# RemoteControl.net
KiCad netlist of a schematic drawn in Altium Designer
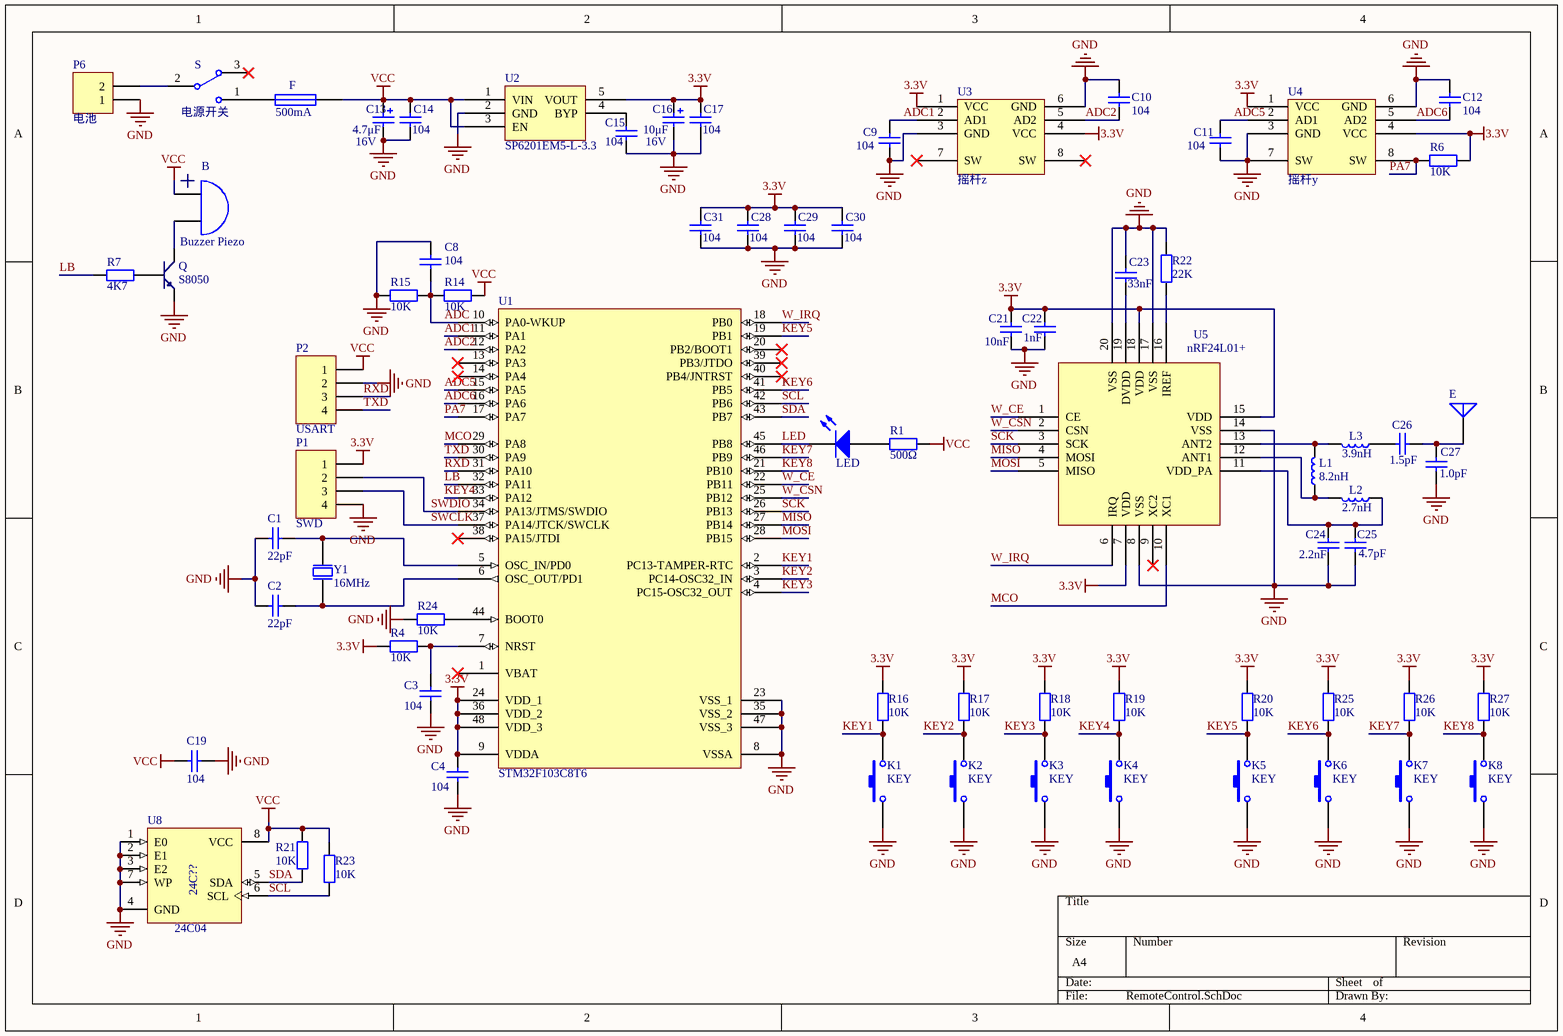
[diagram p0: RemoteControl.SchDoc]

(export (version "E")
  (design (tool "Eeschema 10.0.6"))
  (components
    (comp (ref "B")
      (value "Buzzer Piezo")
      (footprint "BUZZER")
      (description "Electrical Bell")
      (fields (field (name "PUBLISHER") "Altium Limited"))
      (libsource (lib "mini四轴") (part "Buzzer"))
    )
    (comp (ref "C1")
      (value "22pF")
      (footprint "CC1608-0603")
      (description "Capacitor")
      (fields (field (name "PUBLISHER") "Altium Limited"))
      (libsource (lib "mini四轴") (part "Cap"))
    )
    (comp (ref "C2")
      (value "22pF")
      (footprint "CC1608-0603")
      (description "Capacitor")
      (fields (field (name "PUBLISHER") "Altium Limited"))
      (libsource (lib "mini四轴") (part "Cap"))
    )
    (comp (ref "C3")
      (value "104")
      (footprint "CC1608-0603")
      (description "Capacitor")
      (fields (field (name "PUBLISHER") "Altium Limited"))
      (libsource (lib "mini四轴") (part "Cap"))
    )
    (comp (ref "C4")
      (value "104")
      (footprint "CC1608-0603")
      (description "Capacitor")
      (fields (field (name "PUBLISHER") "Altium Limited"))
      (libsource (lib "mini四轴") (part "Cap"))
    )
    (comp (ref "C8")
      (value "104")
      (footprint "CC1608-0603")
      (description "Capacitor")
      (fields (field (name "PUBLISHER") "Altium Limited"))
      (libsource (lib "mini四轴") (part "Cap"))
    )
    (comp (ref "C9")
      (value "104")
      (footprint "CC1608-0603")
      (description "Capacitor")
      (fields (field (name "PUBLISHER") "Altium Limited"))
      (libsource (lib "mini四轴") (part "Cap"))
    )
    (comp (ref "C10")
      (value "104")
      (footprint "CC1608-0603")
      (description "Capacitor")
      (fields (field (name "PUBLISHER") "Altium Limited"))
      (libsource (lib "mini四轴") (part "Cap"))
    )
    (comp (ref "C11")
      (value "104")
      (footprint "CC1608-0603")
      (description "Capacitor")
      (fields (field (name "PUBLISHER") "Altium Limited"))
      (libsource (lib "mini四轴") (part "Cap"))
    )
    (comp (ref "C12")
      (value "104")
      (footprint "CC1608-0603")
      (description "Capacitor")
      (fields (field (name "PUBLISHER") "Altium Limited"))
      (libsource (lib "mini四轴") (part "Cap"))
    )
    (comp (ref "C13")
      (value "4.7μF")
      (footprint "TAN-A-3216")
      (description "Polarized Capacitor (Radial)")
      (fields (field (name "VOLTAGE") "16V") (field (name "PUBLISHER") "Altium Limited"))
      (libsource (lib "我的集成库1") (part "Cap Tan"))
    )
    (comp (ref "C14")
      (value "104")
      (footprint "CC1608-0603")
      (description "Capacitor")
      (fields (field (name "PUBLISHER") "Altium Limited"))
      (libsource (lib "mini四轴") (part "Cap"))
    )
    (comp (ref "C15")
      (value "104")
      (footprint "CC1608-0603")
      (description "Capacitor")
      (fields (field (name "PUBLISHER") "Altium Limited"))
      (libsource (lib "mini四轴") (part "Cap"))
    )
    (comp (ref "C16")
      (value "10μF")
      (footprint "TAN-A-3216")
      (description "Polarized Capacitor (Radial)")
      (fields (field (name "VOLTAGE") "16V") (field (name "PUBLISHER") "Altium Limited"))
      (libsource (lib "我的集成库1") (part "Cap Tan"))
    )
    (comp (ref "C17")
      (value "104")
      (footprint "CC1608-0603")
      (description "Capacitor")
      (fields (field (name "PUBLISHER") "Altium Limited"))
      (libsource (lib "mini四轴") (part "Cap"))
    )
    (comp (ref "C19")
      (value "104")
      (footprint "CC1608-0603")
      (description "Polarized Capacitor (Radial)")
      (fields (field (name "PUBLISHER") "Altium Limited"))
      (libsource (lib "我的集成库1") (part "Cap Chip"))
    )
    (comp (ref "C21")
      (value "10nF")
      (footprint "CC1608-0603")
      (description "Capacitor")
      (fields (field (name "PUBLISHER") "Altium Limited"))
      (libsource (lib "mini四轴") (part "Cap"))
    )
    (comp (ref "C22")
      (value "1nF")
      (footprint "CC1608-0603")
      (description "Capacitor")
      (fields (field (name "PUBLISHER") "Altium Limited"))
      (libsource (lib "mini四轴") (part "Cap"))
    )
    (comp (ref "C23")
      (value "33nF")
      (footprint "CC1608-0603")
      (description "Capacitor")
      (fields (field (name "PUBLISHER") "Altium Limited"))
      (libsource (lib "mini四轴") (part "Cap"))
    )
    (comp (ref "C24")
      (value "2.2nF")
      (footprint "CC1608-0603")
      (description "Capacitor")
      (fields (field (name "PUBLISHER") "Altium Limited"))
      (libsource (lib "mini四轴") (part "Cap"))
    )
    (comp (ref "C25")
      (value "4.7pF")
      (footprint "CC1608-0603")
      (description "Capacitor")
      (fields (field (name "PUBLISHER") "Altium Limited"))
      (libsource (lib "mini四轴") (part "Cap"))
    )
    (comp (ref "C26")
      (value "1.5pF")
      (footprint "CC1608-0603")
      (description "Capacitor")
      (fields (field (name "PUBLISHER") "Altium Limited"))
      (libsource (lib "mini四轴") (part "Cap"))
    )
    (comp (ref "C27")
      (value "1.0pF")
      (footprint "CC1608-0603")
      (description "Capacitor")
      (fields (field (name "PUBLISHER") "Altium Limited"))
      (libsource (lib "mini四轴") (part "Cap"))
    )
    (comp (ref "C28")
      (value "104")
      (footprint "CC1608-0603")
      (description "Capacitor")
      (fields (field (name "PUBLISHER") "Altium Limited"))
      (libsource (lib "mini四轴") (part "Cap"))
    )
    (comp (ref "C29")
      (value "104")
      (footprint "CC1608-0603")
      (description "Capacitor")
      (fields (field (name "PUBLISHER") "Altium Limited"))
      (libsource (lib "mini四轴") (part "Cap"))
    )
    (comp (ref "C30")
      (value "104")
      (footprint "CC1608-0603")
      (description "Capacitor")
      (fields (field (name "PUBLISHER") "Altium Limited"))
      (libsource (lib "mini四轴") (part "Cap"))
    )
    (comp (ref "C31")
      (value "104")
      (footprint "CC1608-0603")
      (description "Capacitor")
      (fields (field (name "PUBLISHER") "Altium Limited"))
      (libsource (lib "mini四轴") (part "Cap"))
    )
    (comp (ref "E")
      (value "~")
      (footprint "Chip Antenna")
      (description "Generic Antenna")
      (fields (field (name "PUBLISHER") "Altium Limited"))
      (libsource (lib "mini四轴") (part "Antenna"))
    )
    (comp (ref "F")
      (value "500mA")
      (footprint "CR2012-0805")
      (description "Fuse")
      (fields (field (name "PUBLISHER") "Altium Limited"))
      (libsource (lib "我的集成库1") (part "Fuse"))
    )
    (comp (ref "K1") (value "KEY") (footprint "KEY2") (libsource (lib "我的集成库1") (part "KYE")))
    (comp (ref "K2") (value "KEY") (footprint "KEY2") (libsource (lib "我的集成库1") (part "KYE")))
    (comp (ref "K3") (value "KEY") (footprint "KEY2") (libsource (lib "我的集成库1") (part "KYE")))
    (comp (ref "K4") (value "KEY") (footprint "KEY2") (libsource (lib "我的集成库1") (part "KYE")))
    (comp (ref "K5") (value "KEY") (footprint "KEY2") (libsource (lib "我的集成库1") (part "KYE")))
    (comp (ref "K6") (value "KEY") (footprint "KEY2") (libsource (lib "我的集成库1") (part "KYE")))
    (comp (ref "K7") (value "KEY") (footprint "KEY2") (libsource (lib "我的集成库1") (part "KYE")))
    (comp (ref "K8") (value "KEY") (footprint "KEY2") (libsource (lib "我的集成库1") (part "KYE")))
    (comp (ref "L1")
      (value "8.2nH")
      (footprint "CC1608[0603]")
      (description "Inductor")
      (fields (field (name "PUBLISHER") "Altium Limited"))
      (libsource (lib "mini四轴") (part "Inductor"))
    )
    (comp (ref "L2")
      (value "2.7nH")
      (footprint "CC1608[0603]")
      (description "Inductor")
      (fields (field (name "PUBLISHER") "Altium Limited"))
      (libsource (lib "mini四轴") (part "Inductor"))
    )
    (comp (ref "L3")
      (value "3.9nH")
      (footprint "CC1608[0603]")
      (description "Inductor")
      (fields (field (name "PUBLISHER") "Altium Limited"))
      (libsource (lib "mini四轴") (part "Inductor"))
    )
    (comp (ref "LED")
      (value "LED Chip")
      (footprint "CLED1608-0603")
      (description "Typical Chip LED")
      (fields (field (name "PUBLISHER") "Altium Limited"))
      (libsource (lib "我的集成库1") (part "LED Chip"))
    )
    (comp (ref "P1")
      (value "SWD")
      (footprint "HDR1X4")
      (description "Header, 4-Pin")
      (fields (field (name "PUBLISHER") "Altium Limited"))
      (libsource (lib "我的集成库1") (part "Header 4"))
    )
    (comp (ref "P2")
      (value "USART")
      (footprint "HDR1X4")
      (description "Header, 4-Pin")
      (fields (field (name "PUBLISHER") "Altium Limited"))
      (libsource (lib "我的集成库1") (part "Header 4"))
    )
    (comp (ref "P6")
      (value "电池")
      (footprint "HDR1X2")
      (description "Header, 2-Pin")
      (fields (field (name "PUBLISHER") "Altium Limited"))
      (libsource (lib "我的集成库1") (part "Header 2"))
    )
    (comp (ref "Q")
      (value "S8050")
      (footprint "SOT-23")
      (description "8050/BCW846/BCW847")
      (libsource (lib "战舰STM32开发板底板封装库") (part "NPN"))
    )
    (comp (ref "R1")
      (value "500Ω")
      (footprint "CR1608-0603")
      (description "Resistor")
      (fields (field (name "PUBLISHER") "Altium Limited"))
      (libsource (lib "") (part "Resistor Chip_2"))
    )
    (comp (ref "R4")
      (value "10K")
      (footprint "CR1608-0603")
      (description "Resistor")
      (fields (field (name "PUBLISHER") "Altium Limited"))
      (libsource (lib "") (part "Resistor Chip_3"))
    )
    (comp (ref "R6")
      (value "10K")
      (footprint "CR1608-0603")
      (description "Resistor")
      (fields (field (name "PUBLISHER") "Altium Limited"))
      (libsource (lib "") (part "Resistor Chip_2"))
    )
    (comp (ref "R7")
      (value "4K7")
      (footprint "CR1608-0603")
      (description "Resistor")
      (fields (field (name "Comment") "10K") (field (name "PUBLISHER") "Altium Limited"))
      (libsource (lib "") (part "Resistor Chip_2"))
    )
    (comp (ref "R14")
      (value "10K")
      (footprint "CR1608-0603")
      (description "Resistor")
      (fields (field (name "PUBLISHER") "Altium Limited"))
      (libsource (lib "") (part "Resistor Chip_1"))
    )
    (comp (ref "R15")
      (value "10K")
      (footprint "CR1608-0603")
      (description "Resistor")
      (fields (field (name "PUBLISHER") "Altium Limited"))
      (libsource (lib "") (part "Resistor Chip_1"))
    )
    (comp (ref "R16")
      (value "10K")
      (footprint "CR1608-0603")
      (description "Resistor")
      (fields (field (name "PUBLISHER") "Altium Limited"))
      (libsource (lib "我的集成库1") (part "Resistor Chip"))
    )
    (comp (ref "R17")
      (value "10K")
      (footprint "CR1608-0603")
      (description "Resistor")
      (fields (field (name "PUBLISHER") "Altium Limited"))
      (libsource (lib "我的集成库1") (part "Resistor Chip"))
    )
    (comp (ref "R18")
      (value "10K")
      (footprint "CR1608-0603")
      (description "Resistor")
      (fields (field (name "PUBLISHER") "Altium Limited"))
      (libsource (lib "我的集成库1") (part "Resistor Chip"))
    )
    (comp (ref "R19")
      (value "10K")
      (footprint "CR1608-0603")
      (description "Resistor")
      (fields (field (name "PUBLISHER") "Altium Limited"))
      (libsource (lib "我的集成库1") (part "Resistor Chip"))
    )
    (comp (ref "R20")
      (value "10K")
      (footprint "CR1608-0603")
      (description "Resistor")
      (fields (field (name "PUBLISHER") "Altium Limited"))
      (libsource (lib "我的集成库1") (part "Resistor Chip"))
    )
    (comp (ref "R21")
      (value "10K")
      (footprint "CR1608-0603")
      (description "Resistor")
      (fields (field (name "PUBLISHER") "Altium Limited"))
      (libsource (lib "") (part "Resistor Axial_1"))
    )
    (comp (ref "R22")
      (value "22K")
      (footprint "CR1608-0603")
      (description "Resistor")
      (fields (field (name "PUBLISHER") "Altium Limited"))
      (libsource (lib "我的集成库1") (part "Resistor Chip"))
    )
    (comp (ref "R23")
      (value "10K")
      (footprint "CR1608-0603")
      (description "Resistor")
      (fields (field (name "PUBLISHER") "Altium Limited"))
      (libsource (lib "") (part "Resistor Axial_1"))
    )
    (comp (ref "R24")
      (value "10K")
      (footprint "CR1608-0603")
      (description "Resistor")
      (fields (field (name "PUBLISHER") "Altium Limited"))
      (libsource (lib "!)Miscellaneous Integrated Library") (part "Resistor Axial"))
    )
    (comp (ref "R25")
      (value "10K")
      (footprint "CR1608-0603")
      (description "Resistor")
      (fields (field (name "PUBLISHER") "Altium Limited"))
      (libsource (lib "我的集成库1") (part "Resistor Chip"))
    )
    (comp (ref "R26")
      (value "10K")
      (footprint "CR1608-0603")
      (description "Resistor")
      (fields (field (name "PUBLISHER") "Altium Limited"))
      (libsource (lib "我的集成库1") (part "Resistor Chip"))
    )
    (comp (ref "R27")
      (value "10K")
      (footprint "CR1608-0603")
      (description "Resistor")
      (fields (field (name "PUBLISHER") "Altium Limited"))
      (libsource (lib "我的集成库1") (part "Resistor Chip"))
    )
    (comp (ref "S")
      (value "电源开关")
      (footprint "MSK-12C02-1")
      (description "SPDT Subminiature Toggle Switch, Right Angle Mounting, Vertical Actuation")
      (fields (field (name "PUBLISHER") "Altium Limited"))
      (libsource (lib "mini四轴") (part "SW-SPDT"))
    )
    (comp (ref "U1")
      (value "STM32F103C8T6")
      (footprint "LQFP48_N")
      (description "STM32 ARM-based 32-bit MCU with 64 Kbytes Flash, 48-pin LQFP, Industrial Temperature")
      (fields (field (name "PUBLISHER") "*"))
      (libsource (lib "STM32") (part "STM32F103C8T6"))
    )
    (comp (ref "U2")
      (value "SP6201EM5-L-3.3")
      (footprint "SO-G5/NS")
      (libsource (lib "mini四轴") (part "PAM3101"))
    )
    (comp (ref "U3") (value "摇杆z") (footprint "摇杆") (libsource (lib "mini四轴") (part "摇杆")))
    (comp (ref "U4") (value "摇杆y") (footprint "摇杆") (libsource (lib "mini四轴") (part "摇杆")))
    (comp (ref "U5")
      (value "nRF24L01+")
      (footprint "QFN50P400X400-20V5N")
      (libsource (lib "mini四轴") (part "nRF24L01+"))
    )
    (comp (ref "U8")
      (value "24C04")
      (footprint "SOP-8N")
      (description "??Kbit Serial  Bus EEPROM")
      (fields (field (name "PUBLISHER") "Altium Limited"))
      (libsource (lib "我的集成库1") (part "24CXXSOP"))
    )
    (comp (ref "Y1")
      (value "8MHz")
      (footprint "XTAL-PINGBI")
      (description "Crystal Oscillator")
      (fields (field (name "FREQUENCY") "16MHz") (field (name "PUBLISHER") "Altium Limited"))
      (libsource (lib "我的集成库1") (part "XTAL"))
    )
  )
  (nets
    (net (code "1") (name "/ADC") (class "Default")
      (node (ref "C8") (pin "2") (pinfunction "2_2") (pintype "passive"))
      (node (ref "R14") (pin "2") (pinfunction "2_2") (pintype "passive"))
      (node (ref "R15") (pin "1") (pinfunction "1_1") (pintype "passive"))
      (node (ref "U1") (pin "10") (pinfunction "PA0-WKUP_10") (pintype "bidirectional"))
    )
    (net (code "2") (name "/ADC1") (class "Default")
      (node (ref "C9") (pin "2") (pinfunction "2_2") (pintype "passive"))
      (node (ref "U1") (pin "11") (pinfunction "PA1_11") (pintype "bidirectional"))
      (node (ref "U3") (pin "2") (pinfunction "AD1_2") (pintype "passive"))
    )
    (net (code "3") (name "/ADC2") (class "Default")
      (node (ref "C10") (pin "1") (pinfunction "1_1") (pintype "passive"))
      (node (ref "U1") (pin "12") (pinfunction "PA2_12") (pintype "bidirectional"))
      (node (ref "U3") (pin "5") (pinfunction "AD2_5") (pintype "passive"))
    )
    (net (code "4") (name "/ADC5") (class "Default")
      (node (ref "C11") (pin "2") (pinfunction "2_2") (pintype "passive"))
      (node (ref "U1") (pin "15") (pinfunction "PA5_15") (pintype "bidirectional"))
      (node (ref "U4") (pin "2") (pinfunction "AD1_2") (pintype "passive"))
    )
    (net (code "5") (name "/ADC6") (class "Default")
      (node (ref "C12") (pin "1") (pinfunction "1_1") (pintype "passive"))
      (node (ref "U1") (pin "16") (pinfunction "PA6_16") (pintype "bidirectional"))
      (node (ref "U4") (pin "5") (pinfunction "AD2_5") (pintype "passive"))
    )
    (net (code "6") (name "/KEY1") (class "Default")
      (node (ref "K1") (pin "2") (pinfunction "2_2") (pintype "passive"))
      (node (ref "R16") (pin "1") (pinfunction "1_1") (pintype "passive"))
      (node (ref "U1") (pin "2") (pinfunction "PC13-TAMPER-RTC_2") (pintype "bidirectional"))
    )
    (net (code "7") (name "/KEY2") (class "Default")
      (node (ref "K2") (pin "2") (pinfunction "2_2") (pintype "passive"))
      (node (ref "R17") (pin "1") (pinfunction "1_1") (pintype "passive"))
      (node (ref "U1") (pin "3") (pinfunction "PC14-OSC32_IN_3") (pintype "bidirectional"))
    )
    (net (code "8") (name "/KEY3") (class "Default")
      (node (ref "K3") (pin "2") (pinfunction "2_2") (pintype "passive"))
      (node (ref "R18") (pin "1") (pinfunction "1_1") (pintype "passive"))
      (node (ref "U1") (pin "4") (pinfunction "PC15-OSC32_OUT_4") (pintype "bidirectional"))
    )
    (net (code "9") (name "/KEY4") (class "Default")
      (node (ref "K4") (pin "2") (pinfunction "2_2") (pintype "passive"))
      (node (ref "R19") (pin "1") (pinfunction "1_1") (pintype "passive"))
      (node (ref "U1") (pin "33") (pinfunction "PA12_33") (pintype "bidirectional"))
    )
    (net (code "10") (name "/KEY5") (class "Default")
      (node (ref "K5") (pin "2") (pinfunction "2_2") (pintype "passive"))
      (node (ref "R20") (pin "1") (pinfunction "1_1") (pintype "passive"))
      (node (ref "U1") (pin "19") (pinfunction "PB1_19") (pintype "bidirectional"))
    )
    (net (code "11") (name "/KEY6") (class "Default")
      (node (ref "K6") (pin "2") (pinfunction "2_2") (pintype "passive"))
      (node (ref "R25") (pin "1") (pinfunction "1_1") (pintype "passive"))
      (node (ref "U1") (pin "41") (pinfunction "PB5_41") (pintype "bidirectional"))
    )
    (net (code "12") (name "/KEY7") (class "Default")
      (node (ref "K7") (pin "2") (pinfunction "2_2") (pintype "passive"))
      (node (ref "R26") (pin "1") (pinfunction "1_1") (pintype "passive"))
      (node (ref "U1") (pin "46") (pinfunction "PB9_46") (pintype "bidirectional"))
    )
    (net (code "13") (name "/KEY8") (class "Default")
      (node (ref "K8") (pin "2") (pinfunction "2_2") (pintype "passive"))
      (node (ref "R27") (pin "1") (pinfunction "1_1") (pintype "passive"))
      (node (ref "U1") (pin "21") (pinfunction "PB10_21") (pintype "bidirectional"))
    )
    (net (code "14") (name "/LB") (class "Default")
      (node (ref "R7") (pin "2") (pinfunction "2_2") (pintype "passive"))
      (node (ref "U1") (pin "32") (pinfunction "PA11_32") (pintype "bidirectional"))
    )
    (net (code "15") (name "/LED") (class "Default")
      (node (ref "LED") (pin "2") (pinfunction "K_2") (pintype "passive"))
      (node (ref "U1") (pin "45") (pinfunction "PB8_45") (pintype "bidirectional"))
    )
    (net (code "16") (name "/MCO") (class "Default")
      (node (ref "U1") (pin "29") (pinfunction "PA8_29") (pintype "bidirectional"))
      (node (ref "U5") (pin "10") (pinfunction "XC1_10") (pintype "passive"))
    )
    (net (code "17") (name "/MISO") (class "Default")
      (node (ref "U1") (pin "27") (pinfunction "PB14_27") (pintype "bidirectional"))
      (node (ref "U5") (pin "4") (pinfunction "MOSI_4") (pintype "passive"))
    )
    (net (code "18") (name "/MOSI") (class "Default")
      (node (ref "U1") (pin "28") (pinfunction "PB15_28") (pintype "bidirectional"))
      (node (ref "U5") (pin "5") (pinfunction "MISO_5") (pintype "passive"))
    )
    (net (code "19") (name "/PA7") (class "Default")
      (node (ref "R6") (pin "2") (pinfunction "2_2") (pintype "passive"))
      (node (ref "U1") (pin "17") (pinfunction "PA7_17") (pintype "bidirectional"))
      (node (ref "U4") (pin "8") (pinfunction "SW_8") (pintype "passive"))
    )
    (net (code "20") (name "/RXD") (class "Default")
      (node (ref "P2") (pin "3") (pinfunction "3_3") (pintype "passive"))
      (node (ref "U1") (pin "31") (pinfunction "PA10_31") (pintype "bidirectional"))
    )
    (net (code "21") (name "/SCK") (class "Default")
      (node (ref "U1") (pin "26") (pinfunction "PB13_26") (pintype "bidirectional"))
      (node (ref "U5") (pin "3") (pinfunction "SCK_3") (pintype "passive"))
    )
    (net (code "22") (name "/SCL") (class "Default")
      (node (ref "R23") (pin "1") (pinfunction "1_1") (pintype "passive"))
      (node (ref "U1") (pin "42") (pinfunction "PB6_42") (pintype "bidirectional"))
      (node (ref "U8") (pin "6") (pinfunction "SCL_6") (pintype "input"))
    )
    (net (code "23") (name "/SDA") (class "Default")
      (node (ref "R21") (pin "1") (pinfunction "1_1") (pintype "passive"))
      (node (ref "U1") (pin "43") (pinfunction "PB7_43") (pintype "bidirectional"))
      (node (ref "U8") (pin "5") (pinfunction "SDA_5") (pintype "bidirectional"))
    )
    (net (code "24") (name "/SWCLK") (class "Default")
      (node (ref "P1") (pin "3") (pinfunction "3_3") (pintype "passive"))
      (node (ref "U1") (pin "37") (pinfunction "PA14/JTCK/SWCLK_37") (pintype "bidirectional"))
    )
    (net (code "25") (name "/SWDIO") (class "Default")
      (node (ref "P1") (pin "2") (pinfunction "2_2") (pintype "passive"))
      (node (ref "U1") (pin "34") (pinfunction "PA13/JTMS/SWDIO_34") (pintype "bidirectional"))
    )
    (net (code "26") (name "/TXD") (class "Default")
      (node (ref "P2") (pin "4") (pinfunction "4_4") (pintype "passive"))
      (node (ref "U1") (pin "30") (pinfunction "PA9_30") (pintype "bidirectional"))
    )
    (net (code "27") (name "/W_CE") (class "Default")
      (node (ref "U1") (pin "22") (pinfunction "PB11_22") (pintype "bidirectional"))
      (node (ref "U5") (pin "1") (pinfunction "CE_1") (pintype "passive"))
    )
    (net (code "28") (name "/W_CSN") (class "Default")
      (node (ref "U1") (pin "25") (pinfunction "PB12_25") (pintype "bidirectional"))
      (node (ref "U5") (pin "2") (pinfunction "CSN_2") (pintype "passive"))
    )
    (net (code "29") (name "/W_IRQ") (class "Default")
      (node (ref "U1") (pin "18") (pinfunction "PB0_18") (pintype "bidirectional"))
      (node (ref "U5") (pin "6") (pinfunction "IRQ_6") (pintype "passive"))
    )
    (net (code "30") (name "3.3V") (class "Default")
      (node (ref "C16") (pin "2") (pinfunction "1_2") (pintype "passive"))
      (node (ref "C17") (pin "2") (pinfunction "2_2") (pintype "passive"))
      (node (ref "C21") (pin "1") (pinfunction "1_1") (pintype "passive"))
      (node (ref "C22") (pin "1") (pinfunction "1_1") (pintype "passive"))
      (node (ref "C28") (pin "2") (pinfunction "2_2") (pintype "passive"))
      (node (ref "C29") (pin "2") (pinfunction "2_2") (pintype "passive"))
      (node (ref "C30") (pin "2") (pinfunction "2_2") (pintype "passive"))
      (node (ref "C31") (pin "2") (pinfunction "2_2") (pintype "passive"))
      (node (ref "C4") (pin "2") (pinfunction "2_2") (pintype "passive"))
      (node (ref "P1") (pin "1") (pinfunction "1_1") (pintype "passive"))
      (node (ref "R16") (pin "2") (pinfunction "2_2") (pintype "passive"))
      (node (ref "R17") (pin "2") (pinfunction "2_2") (pintype "passive"))
      (node (ref "R18") (pin "2") (pinfunction "2_2") (pintype "passive"))
      (node (ref "R19") (pin "2") (pinfunction "2_2") (pintype "passive"))
      (node (ref "R20") (pin "2") (pinfunction "2_2") (pintype "passive"))
      (node (ref "R25") (pin "2") (pinfunction "2_2") (pintype "passive"))
      (node (ref "R26") (pin "2") (pinfunction "2_2") (pintype "passive"))
      (node (ref "R27") (pin "2") (pinfunction "2_2") (pintype "passive"))
      (node (ref "R4") (pin "1") (pinfunction "1_1") (pintype "passive"))
      (node (ref "R6") (pin "1") (pinfunction "1_1") (pintype "passive"))
      (node (ref "U1") (pin "24") (pinfunction "VDD_1_24") (pintype "power_in"))
      (node (ref "U1") (pin "36") (pinfunction "VDD_2_36") (pintype "power_in"))
      (node (ref "U1") (pin "48") (pinfunction "VDD_3_48") (pintype "power_in"))
      (node (ref "U1") (pin "9") (pinfunction "VDDA_9") (pintype "power_in"))
      (node (ref "U2") (pin "5") (pinfunction "VOUT_5") (pintype "passive"))
      (node (ref "U3") (pin "1") (pinfunction "VCC_1") (pintype "passive"))
      (node (ref "U3") (pin "4") (pinfunction "VCC_4") (pintype "passive"))
      (node (ref "U4") (pin "1") (pinfunction "VCC_1") (pintype "passive"))
      (node (ref "U4") (pin "4") (pinfunction "VCC_4") (pintype "passive"))
      (node (ref "U5") (pin "15") (pinfunction "VDD_15") (pintype "passive"))
      (node (ref "U5") (pin "18") (pinfunction "VDD_18") (pintype "passive"))
      (node (ref "U5") (pin "7") (pinfunction "VDD_7") (pintype "passive"))
    )
    (net (code "31") (name "GND") (class "Default")
      (node (ref "C1") (pin "1") (pinfunction "1_1") (pintype "passive"))
      (node (ref "C10") (pin "2") (pinfunction "2_2") (pintype "passive"))
      (node (ref "C11") (pin "1") (pinfunction "1_1") (pintype "passive"))
      (node (ref "C12") (pin "2") (pinfunction "2_2") (pintype "passive"))
      (node (ref "C13") (pin "1") (pinfunction "2_1") (pintype "passive"))
      (node (ref "C14") (pin "1") (pinfunction "1_1") (pintype "passive"))
      (node (ref "C15") (pin "1") (pinfunction "1_1") (pintype "passive"))
      (node (ref "C16") (pin "1") (pinfunction "2_1") (pintype "passive"))
      (node (ref "C17") (pin "1") (pinfunction "1_1") (pintype "passive"))
      (node (ref "C19") (pin "2") (pinfunction "2_2") (pintype "passive"))
      (node (ref "C2") (pin "1") (pinfunction "1_1") (pintype "passive"))
      (node (ref "C21") (pin "2") (pinfunction "2_2") (pintype "passive"))
      (node (ref "C22") (pin "2") (pinfunction "2_2") (pintype "passive"))
      (node (ref "C23") (pin "1") (pinfunction "1_1") (pintype "passive"))
      (node (ref "C24") (pin "2") (pinfunction "2_2") (pintype "passive"))
      (node (ref "C25") (pin "2") (pinfunction "2_2") (pintype "passive"))
      (node (ref "C27") (pin "1") (pinfunction "1_1") (pintype "passive"))
      (node (ref "C28") (pin "1") (pinfunction "1_1") (pintype "passive"))
      (node (ref "C29") (pin "1") (pinfunction "1_1") (pintype "passive"))
      (node (ref "C3") (pin "1") (pinfunction "1_1") (pintype "passive"))
      (node (ref "C30") (pin "1") (pinfunction "1_1") (pintype "passive"))
      (node (ref "C31") (pin "1") (pinfunction "1_1") (pintype "passive"))
      (node (ref "C4") (pin "1") (pinfunction "1_1") (pintype "passive"))
      (node (ref "C8") (pin "1") (pinfunction "1_1") (pintype "passive"))
      (node (ref "C9") (pin "1") (pinfunction "1_1") (pintype "passive"))
      (node (ref "K1") (pin "1") (pinfunction "1_1") (pintype "passive"))
      (node (ref "K2") (pin "1") (pinfunction "1_1") (pintype "passive"))
      (node (ref "K3") (pin "1") (pinfunction "1_1") (pintype "passive"))
      (node (ref "K4") (pin "1") (pinfunction "1_1") (pintype "passive"))
      (node (ref "K5") (pin "1") (pinfunction "1_1") (pintype "passive"))
      (node (ref "K6") (pin "1") (pinfunction "1_1") (pintype "passive"))
      (node (ref "K7") (pin "1") (pinfunction "1_1") (pintype "passive"))
      (node (ref "K8") (pin "1") (pinfunction "1_1") (pintype "passive"))
      (node (ref "P1") (pin "4") (pinfunction "4_4") (pintype "passive"))
      (node (ref "P2") (pin "2") (pinfunction "2_2") (pintype "passive"))
      (node (ref "P6") (pin "1") (pinfunction "1_1") (pintype "passive"))
      (node (ref "Q") (pin "1") (pinfunction "E_1") (pintype "passive"))
      (node (ref "R15") (pin "2") (pinfunction "2_2") (pintype "passive"))
      (node (ref "R22") (pin "2") (pinfunction "2_2") (pintype "passive"))
      (node (ref "R24") (pin "2") (pinfunction "2_2") (pintype "passive"))
      (node (ref "U1") (pin "23") (pinfunction "VSS_1_23") (pintype "power_in"))
      (node (ref "U1") (pin "35") (pinfunction "VSS_2_35") (pintype "power_in"))
      (node (ref "U1") (pin "47") (pinfunction "VSS_3_47") (pintype "power_in"))
      (node (ref "U1") (pin "8") (pinfunction "VSSA_8") (pintype "power_in"))
      (node (ref "U2") (pin "2") (pinfunction "GND_2") (pintype "passive"))
      (node (ref "U3") (pin "3") (pinfunction "GND_3") (pintype "passive"))
      (node (ref "U3") (pin "6") (pinfunction "GND_6") (pintype "passive"))
      (node (ref "U4") (pin "3") (pinfunction "GND_3") (pintype "passive"))
      (node (ref "U4") (pin "6") (pinfunction "GND_6") (pintype "passive"))
      (node (ref "U4") (pin "7") (pinfunction "SW_7") (pintype "passive"))
      (node (ref "U5") (pin "14") (pinfunction "VSS_14") (pintype "passive"))
      (node (ref "U5") (pin "17") (pinfunction "VSS_17") (pintype "passive"))
      (node (ref "U5") (pin "20") (pinfunction "VSS_20") (pintype "passive"))
      (node (ref "U5") (pin "8") (pinfunction "VSS_8") (pintype "passive"))
      (node (ref "U8") (pin "1") (pinfunction "E0_1") (pintype "input"))
      (node (ref "U8") (pin "2") (pinfunction "E1_2") (pintype "input"))
      (node (ref "U8") (pin "3") (pinfunction "E2_3") (pintype "input"))
      (node (ref "U8") (pin "4") (pinfunction "GND_4") (pintype "power_in"))
      (node (ref "U8") (pin "7") (pinfunction "WP_7") (pintype "input"))
    )
    (net (code "32") (name "Net-(B-B)") (class "Default")
      (node (ref "B") (pin "2") (pinfunction "B_2") (pintype "passive"))
      (node (ref "Q") (pin "3") (pinfunction "C_3") (pintype "passive"))
    )
    (net (code "33") (name "Net-(C26-Pad1)") (class "Default")
      (node (ref "C26") (pin "1") (pinfunction "1_1") (pintype "passive"))
      (node (ref "L3") (pin "1") (pinfunction "1_1") (pintype "passive"))
    )
    (net (code "34") (name "Net-(E-A)") (class "Default")
      (node (ref "C26") (pin "2") (pinfunction "2_2") (pintype "passive"))
      (node (ref "C27") (pin "2") (pinfunction "2_2") (pintype "passive"))
      (node (ref "E") (pin "1") (pinfunction "A_1") (pintype "passive"))
    )
    (net (code "35") (name "Net-(F-Pad1)") (class "Default")
      (node (ref "F") (pin "1") (pinfunction "1_1") (pintype "passive"))
      (node (ref "S") (pin "1") (pinfunction "1_1") (pintype "passive"))
    )
    (net (code "36") (name "Net-(LED-A)") (class "Default")
      (node (ref "LED") (pin "1") (pinfunction "A_1") (pintype "passive"))
      (node (ref "R1") (pin "2") (pinfunction "2_2") (pintype "passive"))
    )
    (net (code "37") (name "Net-(P6-Pad2)") (class "Default")
      (node (ref "P6") (pin "2") (pinfunction "2_2") (pintype "passive"))
      (node (ref "S") (pin "2") (pinfunction "2_2") (pintype "passive"))
    )
    (net (code "38") (name "Net-(Q-B)") (class "Default")
      (node (ref "Q") (pin "2") (pinfunction "B_2") (pintype "passive"))
      (node (ref "R7") (pin "1") (pinfunction "1_1") (pintype "passive"))
    )
    (net (code "39") (name "Net-(U1-BOOT0)") (class "Default")
      (node (ref "R24") (pin "1") (pinfunction "1_1") (pintype "passive"))
      (node (ref "U1") (pin "44") (pinfunction "BOOT0_44") (pintype "input"))
    )
    (net (code "40") (name "Net-(U1-NRST)") (class "Default")
      (node (ref "C3") (pin "2") (pinfunction "2_2") (pintype "passive"))
      (node (ref "R4") (pin "2") (pinfunction "2_2") (pintype "passive"))
      (node (ref "U1") (pin "7") (pinfunction "NRST_7") (pintype "bidirectional"))
    )
    (net (code "41") (name "Net-(U1-OSC_IN{slash}PD0)") (class "Default")
      (node (ref "C1") (pin "2") (pinfunction "2_2") (pintype "passive"))
      (node (ref "U1") (pin "5") (pinfunction "OSC_IN/PD0_5") (pintype "input"))
      (node (ref "Y1") (pin "2") (pinfunction "OSC2_2") (pintype "passive"))
    )
    (net (code "42") (name "Net-(U1-OSC_OUT{slash}PD1)") (class "Default")
      (node (ref "C2") (pin "2") (pinfunction "2_2") (pintype "passive"))
      (node (ref "U1") (pin "6") (pinfunction "OSC_OUT/PD1_6") (pintype "output"))
      (node (ref "Y1") (pin "1") (pinfunction "OSC1_1") (pintype "passive"))
    )
    (net (code "43") (name "Net-(U2-BYP)") (class "Default")
      (node (ref "C15") (pin "2") (pinfunction "2_2") (pintype "passive"))
      (node (ref "U2") (pin "4") (pinfunction "BYP_4") (pintype "passive"))
    )
    (net (code "44") (name "Net-(U5-ANT1)") (class "Default")
      (node (ref "L1") (pin "1") (pinfunction "1_1") (pintype "passive"))
      (node (ref "L2") (pin "2") (pinfunction "2_2") (pintype "passive"))
      (node (ref "U5") (pin "12") (pinfunction "ANT1_12") (pintype "passive"))
    )
    (net (code "45") (name "Net-(U5-ANT2)") (class "Default")
      (node (ref "L1") (pin "2") (pinfunction "2_2") (pintype "passive"))
      (node (ref "L3") (pin "2") (pinfunction "2_2") (pintype "passive"))
      (node (ref "U5") (pin "13") (pinfunction "ANT2_13") (pintype "passive"))
    )
    (net (code "46") (name "Net-(U5-DVDD)") (class "Default")
      (node (ref "C23") (pin "2") (pinfunction "2_2") (pintype "passive"))
      (node (ref "U5") (pin "19") (pinfunction "DVDD_19") (pintype "passive"))
    )
    (net (code "47") (name "Net-(U5-IREF)") (class "Default")
      (node (ref "R22") (pin "1") (pinfunction "1_1") (pintype "passive"))
      (node (ref "U5") (pin "16") (pinfunction "IREF_16") (pintype "passive"))
    )
    (net (code "48") (name "Net-(U5-VDD_PA)") (class "Default")
      (node (ref "C24") (pin "1") (pinfunction "1_1") (pintype "passive"))
      (node (ref "C25") (pin "1") (pinfunction "1_1") (pintype "passive"))
      (node (ref "L2") (pin "1") (pinfunction "1_1") (pintype "passive"))
      (node (ref "U5") (pin "11") (pinfunction "VDD_PA_11") (pintype "passive"))
    )
    (net (code "49") (name "VCC") (class "Default")
      (node (ref "B") (pin "1") (pinfunction "A_1") (pintype "passive"))
      (node (ref "C13") (pin "2") (pinfunction "1_2") (pintype "passive"))
      (node (ref "C14") (pin "2") (pinfunction "2_2") (pintype "passive"))
      (node (ref "C19") (pin "1") (pinfunction "1_1") (pintype "passive"))
      (node (ref "F") (pin "2") (pinfunction "2_2") (pintype "passive"))
      (node (ref "P2") (pin "1") (pinfunction "1_1") (pintype "passive"))
      (node (ref "R1") (pin "1") (pinfunction "1_1") (pintype "passive"))
      (node (ref "R14") (pin "1") (pinfunction "1_1") (pintype "passive"))
      (node (ref "R21") (pin "2") (pinfunction "2_2") (pintype "passive"))
      (node (ref "R23") (pin "2") (pinfunction "2_2") (pintype "passive"))
      (node (ref "U2") (pin "1") (pinfunction "VIN_1") (pintype "passive"))
      (node (ref "U2") (pin "3") (pinfunction "EN_3") (pintype "passive"))
      (node (ref "U8") (pin "8") (pinfunction "VCC_8") (pintype "power_in"))
    )
    (net (code "50") (name "unconnected-(S-Pad3)") (class "Default")
      (node (ref "S") (pin "3") (pinfunction "3_3") (pintype "passive+no_connect"))
    )
    (net (code "51") (name "unconnected-(U1-PA3-Pad13)") (class "Default")
      (node (ref "U1") (pin "13") (pinfunction "PA3_13") (pintype "bidirectional+no_connect"))
    )
    (net (code "52") (name "unconnected-(U1-PA4-Pad14)") (class "Default")
      (node (ref "U1") (pin "14") (pinfunction "PA4_14") (pintype "bidirectional+no_connect"))
    )
    (net (code "53") (name "unconnected-(U1-PA15{slash}JTDI-Pad38)") (class "Default")
      (node (ref "U1") (pin "38") (pinfunction "PA15/JTDI_38") (pintype "bidirectional+no_connect"))
    )
    (net (code "54") (name "unconnected-(U1-PB2{slash}BOOT1-Pad20)") (class "Default")
      (node (ref "U1") (pin "20") (pinfunction "PB2/BOOT1_20") (pintype "bidirectional+no_connect"))
    )
    (net (code "55") (name "unconnected-(U1-PB3{slash}JTDO-Pad39)") (class "Default")
      (node (ref "U1") (pin "39") (pinfunction "PB3/JTDO_39") (pintype "bidirectional+no_connect"))
    )
    (net (code "56") (name "unconnected-(U1-PB4{slash}JNTRST-Pad40)") (class "Default")
      (node (ref "U1") (pin "40") (pinfunction "PB4/JNTRST_40") (pintype "bidirectional+no_connect"))
    )
    (net (code "57") (name "unconnected-(U1-VBAT-Pad1)") (class "Default")
      (node (ref "U1") (pin "1") (pinfunction "VBAT_1") (pintype "power_in+no_connect"))
    )
    (net (code "58") (name "unconnected-(U3-SW-Pad7)") (class "Default")
      (node (ref "U3") (pin "7") (pinfunction "SW_7") (pintype "passive+no_connect"))
    )
    (net (code "59") (name "unconnected-(U3-SW-Pad8)") (class "Default")
      (node (ref "U3") (pin "8") (pinfunction "SW_8") (pintype "passive+no_connect"))
    )
    (net (code "60") (name "unconnected-(U5-XC2-Pad9)") (class "Default")
      (node (ref "U5") (pin "9") (pinfunction "XC2_9") (pintype "passive+no_connect"))
    )
  )
)
